# tweeq-extMod_mTouch_2chLinearE.net
KiCad netlist of a schematic drawn in EAGLE
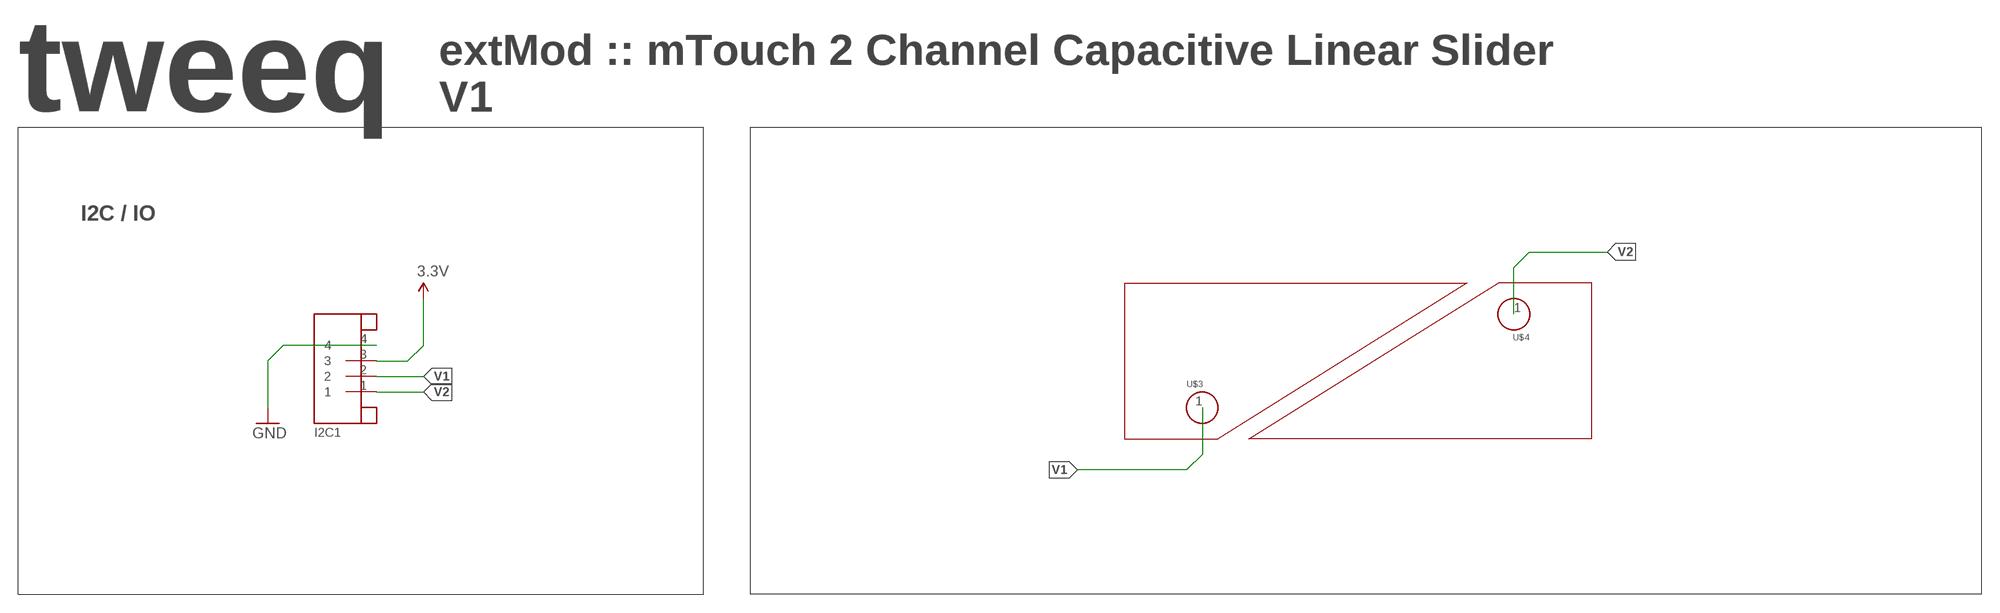
[diagram p0: schematic, sheet 1]

(export (version "E")
  (design (tool "Eeschema 10.0.6"))
  (components
    (comp (ref "I2C1")
      (value "JST-4PINSH")
      (footprint "eagle-import:SH1.0-4PIN")
      (libsource (lib "eagle-import") (part "JST-4PINSH"))
    )
    (comp (ref "U$3")
      (value "MTOUCH_VIA")
      (footprint "eagle-import:MTOUCH_VIA")
      (libsource (lib "eagle-import") (part "MTOUCH_VIA"))
    )
    (comp (ref "U$4")
      (value "MTOUCH_VIA")
      (footprint "eagle-import:MTOUCH_VIA")
      (libsource (lib "eagle-import") (part "MTOUCH_VIA"))
    )
  )
  (nets
    (net (code "1") (name "3.3V") (class "Default")
      (node (ref "I2C1") (pin "3") (pinfunction "3_3") (pintype "bidirectional"))
    )
    (net (code "2") (name "GND") (class "Default")
      (node (ref "I2C1") (pin "4") (pinfunction "4_4") (pintype "bidirectional"))
    )
    (net (code "3") (name "V1") (class "Default")
      (node (ref "I2C1") (pin "2") (pinfunction "2_2") (pintype "bidirectional"))
      (node (ref "U$3") (pin "1") (pinfunction "1_1") (pintype "bidirectional"))
    )
    (net (code "4") (name "V2") (class "Default")
      (node (ref "I2C1") (pin "1") (pinfunction "1_1") (pintype "bidirectional"))
      (node (ref "U$4") (pin "1") (pinfunction "1_1") (pintype "bidirectional"))
    )
  )
)
